# yyb_v2_Leds.net
KiCad netlist of a schematic drawn in Altium Designer
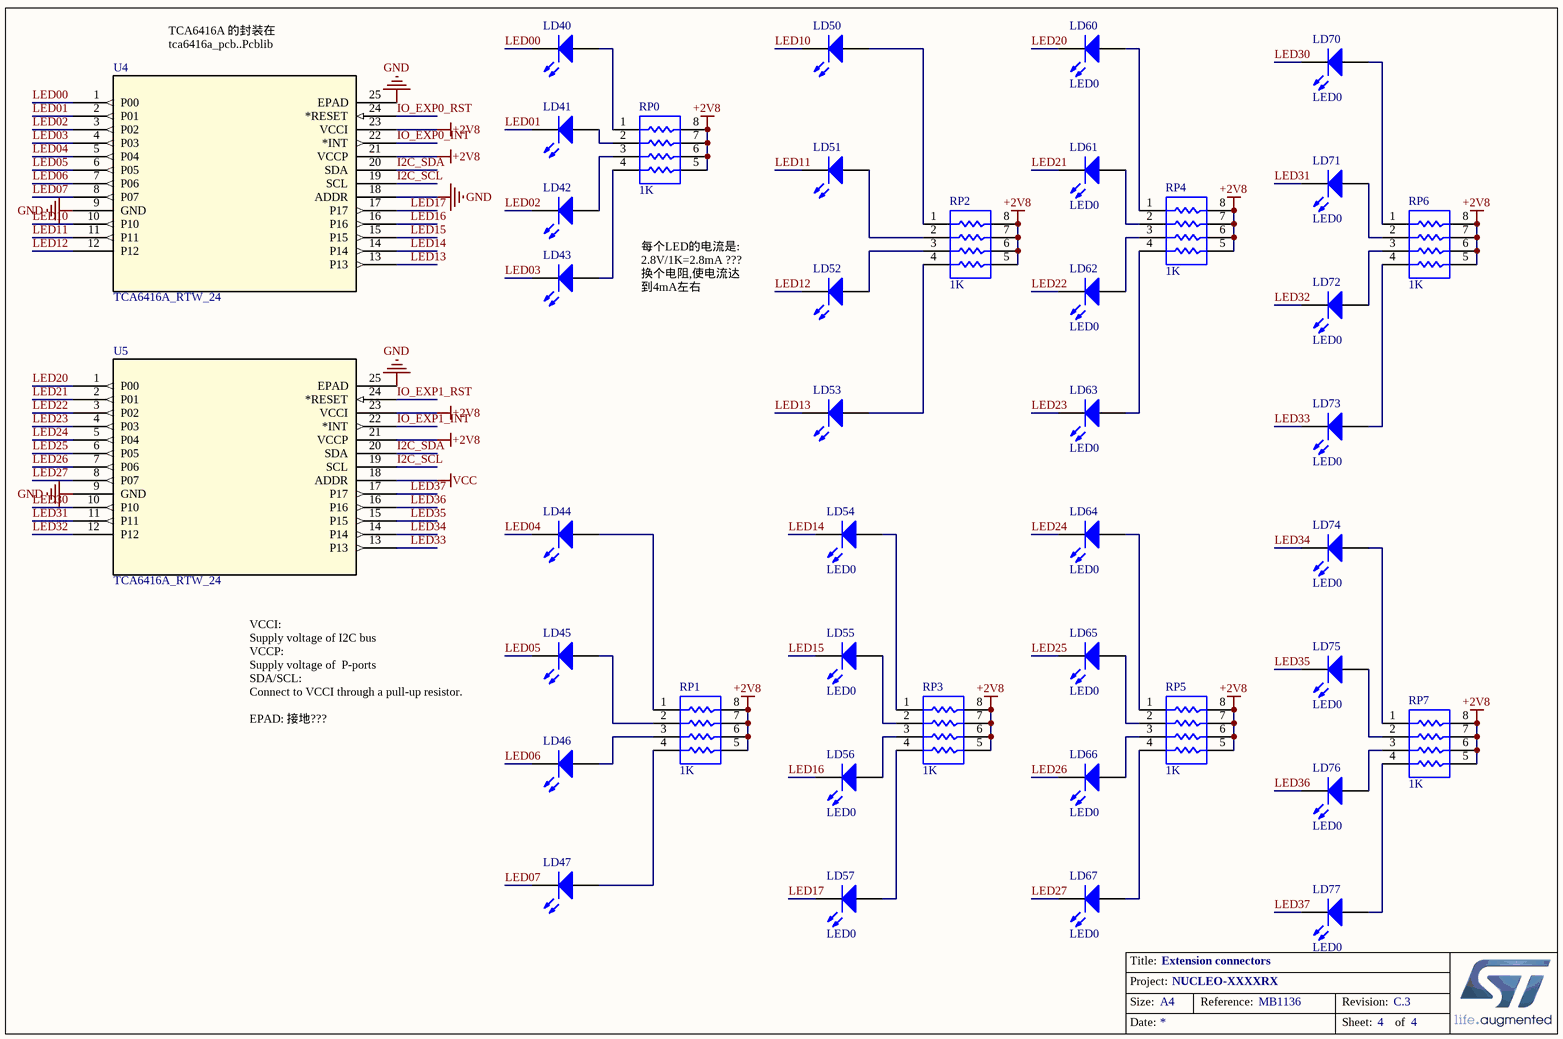
[diagram p0: yyb_v2_Leds.SchDoc]

(export (version "E")
  (design (tool "Eeschema 10.0.6"))
  (components
    (comp (ref "LD40")
      (value "LED0")
      (footprint "LED5")
      (description "Typical INFRARED GaAs LED")
      (fields (field (name "PUBLISHER") "Altium Limited"))
      (libsource (lib "Miscellaneous Devices") (part "LED0"))
    )
    (comp (ref "LD41")
      (value "LED0")
      (footprint "LED5")
      (description "Typical INFRARED GaAs LED")
      (fields (field (name "PUBLISHER") "Altium Limited"))
      (libsource (lib "Miscellaneous Devices") (part "LED0"))
    )
    (comp (ref "LD42")
      (value "LED0")
      (footprint "LED5")
      (description "Typical INFRARED GaAs LED")
      (fields (field (name "PUBLISHER") "Altium Limited"))
      (libsource (lib "Miscellaneous Devices") (part "LED0"))
    )
    (comp (ref "LD43")
      (value "LED0")
      (footprint "LED5")
      (description "Typical INFRARED GaAs LED")
      (fields (field (name "PUBLISHER") "Altium Limited"))
      (libsource (lib "Miscellaneous Devices") (part "LED0"))
    )
    (comp (ref "LD44")
      (value "LED0")
      (footprint "LED-0")
      (description "Typical INFRARED GaAs LED")
      (fields (field (name "PUBLISHER") "Altium Limited"))
      (libsource (lib "Miscellaneous Devices") (part "LED0"))
    )
    (comp (ref "LD45")
      (value "LED0")
      (footprint "LED-0")
      (description "Typical INFRARED GaAs LED")
      (fields (field (name "PUBLISHER") "Altium Limited"))
      (libsource (lib "Miscellaneous Devices") (part "LED0"))
    )
    (comp (ref "LD46")
      (value "LED0")
      (footprint "LED-0")
      (description "Typical INFRARED GaAs LED")
      (fields (field (name "PUBLISHER") "Altium Limited"))
      (libsource (lib "Miscellaneous Devices") (part "LED0"))
    )
    (comp (ref "LD47")
      (value "LED0")
      (footprint "LED-0")
      (description "Typical INFRARED GaAs LED")
      (fields (field (name "PUBLISHER") "Altium Limited"))
      (libsource (lib "Miscellaneous Devices") (part "LED0"))
    )
    (comp (ref "LD50")
      (value "LED0")
      (footprint "LED-0")
      (description "Typical INFRARED GaAs LED")
      (fields (field (name "PUBLISHER") "Altium Limited"))
      (libsource (lib "Miscellaneous Devices") (part "LED0"))
    )
    (comp (ref "LD51")
      (value "LED0")
      (footprint "LED-0")
      (description "Typical INFRARED GaAs LED")
      (fields (field (name "PUBLISHER") "Altium Limited"))
      (libsource (lib "Miscellaneous Devices") (part "LED0"))
    )
    (comp (ref "LD52")
      (value "LED0")
      (footprint "LED-0")
      (description "Typical INFRARED GaAs LED")
      (fields (field (name "PUBLISHER") "Altium Limited"))
      (libsource (lib "Miscellaneous Devices") (part "LED0"))
    )
    (comp (ref "LD53")
      (value "LED0")
      (footprint "LED-0")
      (description "Typical INFRARED GaAs LED")
      (fields (field (name "PUBLISHER") "Altium Limited"))
      (libsource (lib "Miscellaneous Devices") (part "LED0"))
    )
    (comp (ref "LD54")
      (value "LED0")
      (footprint "LED5")
      (description "Typical INFRARED GaAs LED")
      (fields (field (name "PUBLISHER") "Altium Limited"))
      (libsource (lib "Miscellaneous Devices") (part "LED0"))
    )
    (comp (ref "LD55")
      (value "LED0")
      (footprint "LED5")
      (description "Typical INFRARED GaAs LED")
      (fields (field (name "PUBLISHER") "Altium Limited"))
      (libsource (lib "Miscellaneous Devices") (part "LED0"))
    )
    (comp (ref "LD56")
      (value "LED0")
      (footprint "LED5")
      (description "Typical INFRARED GaAs LED")
      (fields (field (name "PUBLISHER") "Altium Limited"))
      (libsource (lib "Miscellaneous Devices") (part "LED0"))
    )
    (comp (ref "LD57")
      (value "LED0")
      (footprint "LED5")
      (description "Typical INFRARED GaAs LED")
      (fields (field (name "PUBLISHER") "Altium Limited"))
      (libsource (lib "Miscellaneous Devices") (part "LED0"))
    )
    (comp (ref "LD60")
      (value "LED0")
      (footprint "LED5")
      (description "Typical INFRARED GaAs LED")
      (fields (field (name "PUBLISHER") "Altium Limited"))
      (libsource (lib "Miscellaneous Devices") (part "LED0"))
    )
    (comp (ref "LD61")
      (value "LED0")
      (footprint "LED5")
      (description "Typical INFRARED GaAs LED")
      (fields (field (name "PUBLISHER") "Altium Limited"))
      (libsource (lib "Miscellaneous Devices") (part "LED0"))
    )
    (comp (ref "LD62")
      (value "LED0")
      (footprint "LED5")
      (description "Typical INFRARED GaAs LED")
      (fields (field (name "PUBLISHER") "Altium Limited"))
      (libsource (lib "Miscellaneous Devices") (part "LED0"))
    )
    (comp (ref "LD63")
      (value "LED0")
      (footprint "LED5")
      (description "Typical INFRARED GaAs LED")
      (fields (field (name "PUBLISHER") "Altium Limited"))
      (libsource (lib "Miscellaneous Devices") (part "LED0"))
    )
    (comp (ref "LD64")
      (value "LED0")
      (footprint "LED5")
      (description "Typical INFRARED GaAs LED")
      (fields (field (name "PUBLISHER") "Altium Limited"))
      (libsource (lib "Miscellaneous Devices") (part "LED0"))
    )
    (comp (ref "LD65")
      (value "LED0")
      (footprint "LED5")
      (description "Typical INFRARED GaAs LED")
      (fields (field (name "PUBLISHER") "Altium Limited"))
      (libsource (lib "Miscellaneous Devices") (part "LED0"))
    )
    (comp (ref "LD66")
      (value "LED0")
      (footprint "LED5")
      (description "Typical INFRARED GaAs LED")
      (fields (field (name "PUBLISHER") "Altium Limited"))
      (libsource (lib "Miscellaneous Devices") (part "LED0"))
    )
    (comp (ref "LD67")
      (value "LED0")
      (footprint "LED5")
      (description "Typical INFRARED GaAs LED")
      (fields (field (name "PUBLISHER") "Altium Limited"))
      (libsource (lib "Miscellaneous Devices") (part "LED0"))
    )
    (comp (ref "LD70")
      (value "LED0")
      (footprint "LED5")
      (description "Typical INFRARED GaAs LED")
      (fields (field (name "PUBLISHER") "Altium Limited"))
      (libsource (lib "Miscellaneous Devices") (part "LED0"))
    )
    (comp (ref "LD71")
      (value "LED0")
      (footprint "LED5")
      (description "Typical INFRARED GaAs LED")
      (fields (field (name "PUBLISHER") "Altium Limited"))
      (libsource (lib "Miscellaneous Devices") (part "LED0"))
    )
    (comp (ref "LD72")
      (value "LED0")
      (footprint "LED5")
      (description "Typical INFRARED GaAs LED")
      (fields (field (name "PUBLISHER") "Altium Limited"))
      (libsource (lib "Miscellaneous Devices") (part "LED0"))
    )
    (comp (ref "LD73")
      (value "LED0")
      (footprint "LED5")
      (description "Typical INFRARED GaAs LED")
      (fields (field (name "PUBLISHER") "Altium Limited"))
      (libsource (lib "Miscellaneous Devices") (part "LED0"))
    )
    (comp (ref "LD74")
      (value "LED0")
      (footprint "LED5")
      (description "Typical INFRARED GaAs LED")
      (fields (field (name "PUBLISHER") "Altium Limited"))
      (libsource (lib "Miscellaneous Devices") (part "LED0"))
    )
    (comp (ref "LD75")
      (value "LED0")
      (footprint "LED5")
      (description "Typical INFRARED GaAs LED")
      (fields (field (name "PUBLISHER") "Altium Limited"))
      (libsource (lib "Miscellaneous Devices") (part "LED0"))
    )
    (comp (ref "LD76")
      (value "LED0")
      (footprint "LED5")
      (description "Typical INFRARED GaAs LED")
      (fields (field (name "PUBLISHER") "Altium Limited"))
      (libsource (lib "Miscellaneous Devices") (part "LED0"))
    )
    (comp (ref "LD77")
      (value "LED0")
      (footprint "LED5")
      (description "Typical INFRARED GaAs LED")
      (fields (field (name "PUBLISHER") "Altium Limited"))
      (libsource (lib "Miscellaneous Devices") (part "LED0"))
    )
    (comp (ref "RP0") (value "1K") (footprint "4P8") (libsource (lib "*") (part "RESPACK3_1")))
    (comp (ref "RP1") (value "1K") (footprint "4P8") (libsource (lib "*") (part "RESPACK3_1")))
    (comp (ref "RP2") (value "1K") (footprint "4P8") (libsource (lib "*") (part "RESPACK3_1")))
    (comp (ref "RP3") (value "1K") (footprint "4P8") (libsource (lib "*") (part "RESPACK3_1")))
    (comp (ref "RP4") (value "1K") (footprint "4P8") (libsource (lib "*") (part "RESPACK3_1")))
    (comp (ref "RP5") (value "1K") (footprint "4P8") (libsource (lib "*") (part "RESPACK3_1")))
    (comp (ref "RP6") (value "1K") (footprint "4P8") (libsource (lib "*") (part "RESPACK3_1")))
    (comp (ref "RP7") (value "1K") (footprint "4P8") (libsource (lib "*") (part "RESPACK3_1")))
    (comp (ref "U4")
      (value "TCA6416A_RTW_24")
      (footprint "RTW24_2P45X2P45")
      (description "Imported")
      (fields
        (field (name "MANUFACTURER") "Texas Instruments")
        (field (name "GENERIC_PART_NUMBER") "TCA6416A")
      )
      (libsource (lib "yyb_sch_layout_v2") (part "TCA6416A_RTW_24"))
    )
    (comp (ref "U5")
      (value "TCA6416A_RTW_24")
      (footprint "RTW24_2P45X2P45")
      (description "Imported")
      (fields
        (field (name "MANUFACTURER") "Texas Instruments")
        (field (name "GENERIC_PART_NUMBER") "TCA6416A")
      )
      (libsource (lib "yyb_sch_layout_v2") (part "TCA6416A_RTW_24"))
    )
  )
  (nets
    (net (code "1") (name "+2V8") (class "Default")
      (node (ref "RP0") (pin "5") (pinfunction "5_5") (pintype "passive"))
      (node (ref "RP0") (pin "6") (pinfunction "6_6") (pintype "passive"))
      (node (ref "RP0") (pin "7") (pinfunction "7_7") (pintype "passive"))
      (node (ref "RP0") (pin "8") (pinfunction "8_8") (pintype "passive"))
      (node (ref "RP1") (pin "5") (pinfunction "5_5") (pintype "passive"))
      (node (ref "RP1") (pin "6") (pinfunction "6_6") (pintype "passive"))
      (node (ref "RP1") (pin "7") (pinfunction "7_7") (pintype "passive"))
      (node (ref "RP1") (pin "8") (pinfunction "8_8") (pintype "passive"))
      (node (ref "RP2") (pin "5") (pinfunction "5_5") (pintype "passive"))
      (node (ref "RP2") (pin "6") (pinfunction "6_6") (pintype "passive"))
      (node (ref "RP2") (pin "7") (pinfunction "7_7") (pintype "passive"))
      (node (ref "RP2") (pin "8") (pinfunction "8_8") (pintype "passive"))
      (node (ref "RP3") (pin "5") (pinfunction "5_5") (pintype "passive"))
      (node (ref "RP3") (pin "6") (pinfunction "6_6") (pintype "passive"))
      (node (ref "RP3") (pin "7") (pinfunction "7_7") (pintype "passive"))
      (node (ref "RP3") (pin "8") (pinfunction "8_8") (pintype "passive"))
      (node (ref "RP4") (pin "5") (pinfunction "5_5") (pintype "passive"))
      (node (ref "RP4") (pin "6") (pinfunction "6_6") (pintype "passive"))
      (node (ref "RP4") (pin "7") (pinfunction "7_7") (pintype "passive"))
      (node (ref "RP4") (pin "8") (pinfunction "8_8") (pintype "passive"))
      (node (ref "RP5") (pin "5") (pinfunction "5_5") (pintype "passive"))
      (node (ref "RP5") (pin "6") (pinfunction "6_6") (pintype "passive"))
      (node (ref "RP5") (pin "7") (pinfunction "7_7") (pintype "passive"))
      (node (ref "RP5") (pin "8") (pinfunction "8_8") (pintype "passive"))
      (node (ref "RP6") (pin "5") (pinfunction "5_5") (pintype "passive"))
      (node (ref "RP6") (pin "6") (pinfunction "6_6") (pintype "passive"))
      (node (ref "RP6") (pin "7") (pinfunction "7_7") (pintype "passive"))
      (node (ref "RP6") (pin "8") (pinfunction "8_8") (pintype "passive"))
      (node (ref "RP7") (pin "5") (pinfunction "5_5") (pintype "passive"))
      (node (ref "RP7") (pin "6") (pinfunction "6_6") (pintype "passive"))
      (node (ref "RP7") (pin "7") (pinfunction "7_7") (pintype "passive"))
      (node (ref "RP7") (pin "8") (pinfunction "8_8") (pintype "passive"))
      (node (ref "U4") (pin "21") (pinfunction "VCCP_21") (pintype "power_in"))
      (node (ref "U4") (pin "23") (pinfunction "VCCI_23") (pintype "power_in"))
      (node (ref "U5") (pin "21") (pinfunction "VCCP_21") (pintype "power_in"))
      (node (ref "U5") (pin "23") (pinfunction "VCCI_23") (pintype "power_in"))
    )
    (net (code "2") (name "/I2C_SCL") (class "Default")
      (node (ref "U4") (pin "19") (pinfunction "SCL_19") (pintype "passive"))
      (node (ref "U5") (pin "19") (pinfunction "SCL_19") (pintype "passive"))
    )
    (net (code "3") (name "/I2C_SDA") (class "Default")
      (node (ref "U4") (pin "20") (pinfunction "SDA_20") (pintype "passive"))
      (node (ref "U5") (pin "20") (pinfunction "SDA_20") (pintype "passive"))
    )
    (net (code "4") (name "/IO_EXP0_INT") (class "Default")
      (node (ref "U4") (pin "22") (pinfunction "*INT_22") (pintype "output"))
    )
    (net (code "5") (name "/IO_EXP0_RST") (class "Default")
      (node (ref "U4") (pin "24") (pinfunction "*RESET_24") (pintype "input"))
    )
    (net (code "6") (name "/IO_EXP1_INT") (class "Default")
      (node (ref "U5") (pin "22") (pinfunction "*INT_22") (pintype "output"))
    )
    (net (code "7") (name "/IO_EXP1_RST") (class "Default")
      (node (ref "U5") (pin "24") (pinfunction "*RESET_24") (pintype "input"))
    )
    (net (code "8") (name "/LED00") (class "Default")
      (node (ref "LD40") (pin "2") (pinfunction "K_2") (pintype "passive"))
      (node (ref "U4") (pin "1") (pinfunction "P00_1") (pintype "output"))
    )
    (net (code "9") (name "/LED01") (class "Default")
      (node (ref "LD41") (pin "2") (pinfunction "K_2") (pintype "passive"))
      (node (ref "U4") (pin "2") (pinfunction "P01_2") (pintype "output"))
    )
    (net (code "10") (name "/LED02") (class "Default")
      (node (ref "LD42") (pin "2") (pinfunction "K_2") (pintype "passive"))
      (node (ref "U4") (pin "3") (pinfunction "P02_3") (pintype "output"))
    )
    (net (code "11") (name "/LED03") (class "Default")
      (node (ref "LD43") (pin "2") (pinfunction "K_2") (pintype "passive"))
      (node (ref "U4") (pin "4") (pinfunction "P03_4") (pintype "output"))
    )
    (net (code "12") (name "/LED04") (class "Default")
      (node (ref "LD44") (pin "2") (pinfunction "K_2") (pintype "passive"))
      (node (ref "U4") (pin "5") (pinfunction "P04_5") (pintype "output"))
    )
    (net (code "13") (name "/LED05") (class "Default")
      (node (ref "LD45") (pin "2") (pinfunction "K_2") (pintype "passive"))
      (node (ref "U4") (pin "6") (pinfunction "P05_6") (pintype "output"))
    )
    (net (code "14") (name "/LED06") (class "Default")
      (node (ref "LD46") (pin "2") (pinfunction "K_2") (pintype "passive"))
      (node (ref "U4") (pin "7") (pinfunction "P06_7") (pintype "output"))
    )
    (net (code "15") (name "/LED07") (class "Default")
      (node (ref "LD47") (pin "2") (pinfunction "K_2") (pintype "passive"))
      (node (ref "U4") (pin "8") (pinfunction "P07_8") (pintype "output"))
    )
    (net (code "16") (name "/LED10") (class "Default")
      (node (ref "LD50") (pin "2") (pinfunction "K_2") (pintype "passive"))
      (node (ref "U4") (pin "10") (pinfunction "P10_10") (pintype "output"))
    )
    (net (code "17") (name "/LED11") (class "Default")
      (node (ref "LD51") (pin "2") (pinfunction "K_2") (pintype "passive"))
      (node (ref "U4") (pin "11") (pinfunction "P11_11") (pintype "output"))
    )
    (net (code "18") (name "/LED12") (class "Default")
      (node (ref "LD52") (pin "2") (pinfunction "K_2") (pintype "passive"))
      (node (ref "U4") (pin "12") (pinfunction "P12_12") (pintype "power_in"))
    )
    (net (code "19") (name "/LED13") (class "Default")
      (node (ref "LD53") (pin "2") (pinfunction "K_2") (pintype "passive"))
      (node (ref "U4") (pin "13") (pinfunction "P13_13") (pintype "output"))
    )
    (net (code "20") (name "/LED14") (class "Default")
      (node (ref "LD54") (pin "2") (pinfunction "K_2") (pintype "passive"))
      (node (ref "U4") (pin "14") (pinfunction "P14_14") (pintype "output"))
    )
    (net (code "21") (name "/LED15") (class "Default")
      (node (ref "LD55") (pin "2") (pinfunction "K_2") (pintype "passive"))
      (node (ref "U4") (pin "15") (pinfunction "P15_15") (pintype "output"))
    )
    (net (code "22") (name "/LED16") (class "Default")
      (node (ref "LD56") (pin "2") (pinfunction "K_2") (pintype "passive"))
      (node (ref "U4") (pin "16") (pinfunction "P16_16") (pintype "output"))
    )
    (net (code "23") (name "/LED17") (class "Default")
      (node (ref "LD57") (pin "2") (pinfunction "K_2") (pintype "passive"))
      (node (ref "U4") (pin "17") (pinfunction "P17_17") (pintype "output"))
    )
    (net (code "24") (name "/LED20") (class "Default")
      (node (ref "LD60") (pin "2") (pinfunction "K_2") (pintype "passive"))
      (node (ref "U5") (pin "1") (pinfunction "P00_1") (pintype "output"))
    )
    (net (code "25") (name "/LED21") (class "Default")
      (node (ref "LD61") (pin "2") (pinfunction "K_2") (pintype "passive"))
      (node (ref "U5") (pin "2") (pinfunction "P01_2") (pintype "output"))
    )
    (net (code "26") (name "/LED22") (class "Default")
      (node (ref "LD62") (pin "2") (pinfunction "K_2") (pintype "passive"))
      (node (ref "U5") (pin "3") (pinfunction "P02_3") (pintype "output"))
    )
    (net (code "27") (name "/LED23") (class "Default")
      (node (ref "LD63") (pin "2") (pinfunction "K_2") (pintype "passive"))
      (node (ref "U5") (pin "4") (pinfunction "P03_4") (pintype "output"))
    )
    (net (code "28") (name "/LED24") (class "Default")
      (node (ref "LD64") (pin "2") (pinfunction "K_2") (pintype "passive"))
      (node (ref "U5") (pin "5") (pinfunction "P04_5") (pintype "output"))
    )
    (net (code "29") (name "/LED25") (class "Default")
      (node (ref "LD65") (pin "2") (pinfunction "K_2") (pintype "passive"))
      (node (ref "U5") (pin "6") (pinfunction "P05_6") (pintype "output"))
    )
    (net (code "30") (name "/LED26") (class "Default")
      (node (ref "LD66") (pin "2") (pinfunction "K_2") (pintype "passive"))
      (node (ref "U5") (pin "7") (pinfunction "P06_7") (pintype "output"))
    )
    (net (code "31") (name "/LED27") (class "Default")
      (node (ref "LD67") (pin "2") (pinfunction "K_2") (pintype "passive"))
      (node (ref "U5") (pin "8") (pinfunction "P07_8") (pintype "output"))
    )
    (net (code "32") (name "/LED30") (class "Default")
      (node (ref "LD70") (pin "2") (pinfunction "K_2") (pintype "passive"))
      (node (ref "U5") (pin "10") (pinfunction "P10_10") (pintype "output"))
    )
    (net (code "33") (name "/LED31") (class "Default")
      (node (ref "LD71") (pin "2") (pinfunction "K_2") (pintype "passive"))
      (node (ref "U5") (pin "11") (pinfunction "P11_11") (pintype "output"))
    )
    (net (code "34") (name "/LED32") (class "Default")
      (node (ref "LD72") (pin "2") (pinfunction "K_2") (pintype "passive"))
      (node (ref "U5") (pin "12") (pinfunction "P12_12") (pintype "power_in"))
    )
    (net (code "35") (name "/LED33") (class "Default")
      (node (ref "LD73") (pin "2") (pinfunction "K_2") (pintype "passive"))
      (node (ref "U5") (pin "13") (pinfunction "P13_13") (pintype "output"))
    )
    (net (code "36") (name "/LED34") (class "Default")
      (node (ref "LD74") (pin "2") (pinfunction "K_2") (pintype "passive"))
      (node (ref "U5") (pin "14") (pinfunction "P14_14") (pintype "output"))
    )
    (net (code "37") (name "/LED35") (class "Default")
      (node (ref "LD75") (pin "2") (pinfunction "K_2") (pintype "passive"))
      (node (ref "U5") (pin "15") (pinfunction "P15_15") (pintype "output"))
    )
    (net (code "38") (name "/LED36") (class "Default")
      (node (ref "LD76") (pin "2") (pinfunction "K_2") (pintype "passive"))
      (node (ref "U5") (pin "16") (pinfunction "P16_16") (pintype "output"))
    )
    (net (code "39") (name "/LED37") (class "Default")
      (node (ref "LD77") (pin "2") (pinfunction "K_2") (pintype "passive"))
      (node (ref "U5") (pin "17") (pinfunction "P17_17") (pintype "output"))
    )
    (net (code "40") (name "GND") (class "Default")
      (node (ref "U4") (pin "18") (pinfunction "ADDR_18") (pintype "passive"))
      (node (ref "U4") (pin "25") (pinfunction "EPAD_25") (pintype "passive"))
      (node (ref "U4") (pin "9") (pinfunction "GND_9") (pintype "power_in"))
      (node (ref "U5") (pin "25") (pinfunction "EPAD_25") (pintype "passive"))
      (node (ref "U5") (pin "9") (pinfunction "GND_9") (pintype "power_in"))
    )
    (net (code "41") (name "Net-(LD40-A)") (class "Default")
      (node (ref "LD40") (pin "1") (pinfunction "A_1") (pintype "passive"))
      (node (ref "RP0") (pin "1") (pinfunction "1_1") (pintype "passive"))
    )
    (net (code "42") (name "Net-(LD41-A)") (class "Default")
      (node (ref "LD41") (pin "1") (pinfunction "A_1") (pintype "passive"))
      (node (ref "RP0") (pin "2") (pinfunction "2_2") (pintype "passive"))
    )
    (net (code "43") (name "Net-(LD42-A)") (class "Default")
      (node (ref "LD42") (pin "1") (pinfunction "A_1") (pintype "passive"))
      (node (ref "RP0") (pin "3") (pinfunction "3_3") (pintype "passive"))
    )
    (net (code "44") (name "Net-(LD43-A)") (class "Default")
      (node (ref "LD43") (pin "1") (pinfunction "A_1") (pintype "passive"))
      (node (ref "RP0") (pin "4") (pinfunction "4_4") (pintype "passive"))
    )
    (net (code "45") (name "Net-(LD44-A)") (class "Default")
      (node (ref "LD44") (pin "1") (pinfunction "A_1") (pintype "passive"))
      (node (ref "RP1") (pin "1") (pinfunction "1_1") (pintype "passive"))
    )
    (net (code "46") (name "Net-(LD45-A)") (class "Default")
      (node (ref "LD45") (pin "1") (pinfunction "A_1") (pintype "passive"))
      (node (ref "RP1") (pin "2") (pinfunction "2_2") (pintype "passive"))
    )
    (net (code "47") (name "Net-(LD46-A)") (class "Default")
      (node (ref "LD46") (pin "1") (pinfunction "A_1") (pintype "passive"))
      (node (ref "RP1") (pin "3") (pinfunction "3_3") (pintype "passive"))
    )
    (net (code "48") (name "Net-(LD47-A)") (class "Default")
      (node (ref "LD47") (pin "1") (pinfunction "A_1") (pintype "passive"))
      (node (ref "RP1") (pin "4") (pinfunction "4_4") (pintype "passive"))
    )
    (net (code "49") (name "Net-(LD50-A)") (class "Default")
      (node (ref "LD50") (pin "1") (pinfunction "A_1") (pintype "passive"))
      (node (ref "RP2") (pin "1") (pinfunction "1_1") (pintype "passive"))
    )
    (net (code "50") (name "Net-(LD51-A)") (class "Default")
      (node (ref "LD51") (pin "1") (pinfunction "A_1") (pintype "passive"))
      (node (ref "RP2") (pin "2") (pinfunction "2_2") (pintype "passive"))
    )
    (net (code "51") (name "Net-(LD52-A)") (class "Default")
      (node (ref "LD52") (pin "1") (pinfunction "A_1") (pintype "passive"))
      (node (ref "RP2") (pin "3") (pinfunction "3_3") (pintype "passive"))
    )
    (net (code "52") (name "Net-(LD53-A)") (class "Default")
      (node (ref "LD53") (pin "1") (pinfunction "A_1") (pintype "passive"))
      (node (ref "RP2") (pin "4") (pinfunction "4_4") (pintype "passive"))
    )
    (net (code "53") (name "Net-(LD54-A)") (class "Default")
      (node (ref "LD54") (pin "1") (pinfunction "A_1") (pintype "passive"))
      (node (ref "RP3") (pin "1") (pinfunction "1_1") (pintype "passive"))
    )
    (net (code "54") (name "Net-(LD55-A)") (class "Default")
      (node (ref "LD55") (pin "1") (pinfunction "A_1") (pintype "passive"))
      (node (ref "RP3") (pin "2") (pinfunction "2_2") (pintype "passive"))
    )
    (net (code "55") (name "Net-(LD56-A)") (class "Default")
      (node (ref "LD56") (pin "1") (pinfunction "A_1") (pintype "passive"))
      (node (ref "RP3") (pin "3") (pinfunction "3_3") (pintype "passive"))
    )
    (net (code "56") (name "Net-(LD57-A)") (class "Default")
      (node (ref "LD57") (pin "1") (pinfunction "A_1") (pintype "passive"))
      (node (ref "RP3") (pin "4") (pinfunction "4_4") (pintype "passive"))
    )
    (net (code "57") (name "Net-(LD60-A)") (class "Default")
      (node (ref "LD60") (pin "1") (pinfunction "A_1") (pintype "passive"))
      (node (ref "RP4") (pin "1") (pinfunction "1_1") (pintype "passive"))
    )
    (net (code "58") (name "Net-(LD61-A)") (class "Default")
      (node (ref "LD61") (pin "1") (pinfunction "A_1") (pintype "passive"))
      (node (ref "RP4") (pin "2") (pinfunction "2_2") (pintype "passive"))
    )
    (net (code "59") (name "Net-(LD62-A)") (class "Default")
      (node (ref "LD62") (pin "1") (pinfunction "A_1") (pintype "passive"))
      (node (ref "RP4") (pin "3") (pinfunction "3_3") (pintype "passive"))
    )
    (net (code "60") (name "Net-(LD63-A)") (class "Default")
      (node (ref "LD63") (pin "1") (pinfunction "A_1") (pintype "passive"))
      (node (ref "RP4") (pin "4") (pinfunction "4_4") (pintype "passive"))
    )
    (net (code "61") (name "Net-(LD64-A)") (class "Default")
      (node (ref "LD64") (pin "1") (pinfunction "A_1") (pintype "passive"))
      (node (ref "RP5") (pin "1") (pinfunction "1_1") (pintype "passive"))
    )
    (net (code "62") (name "Net-(LD65-A)") (class "Default")
      (node (ref "LD65") (pin "1") (pinfunction "A_1") (pintype "passive"))
      (node (ref "RP5") (pin "2") (pinfunction "2_2") (pintype "passive"))
    )
    (net (code "63") (name "Net-(LD66-A)") (class "Default")
      (node (ref "LD66") (pin "1") (pinfunction "A_1") (pintype "passive"))
      (node (ref "RP5") (pin "3") (pinfunction "3_3") (pintype "passive"))
    )
    (net (code "64") (name "Net-(LD67-A)") (class "Default")
      (node (ref "LD67") (pin "1") (pinfunction "A_1") (pintype "passive"))
      (node (ref "RP5") (pin "4") (pinfunction "4_4") (pintype "passive"))
    )
    (net (code "65") (name "Net-(LD70-A)") (class "Default")
      (node (ref "LD70") (pin "1") (pinfunction "A_1") (pintype "passive"))
      (node (ref "RP6") (pin "1") (pinfunction "1_1") (pintype "passive"))
    )
    (net (code "66") (name "Net-(LD71-A)") (class "Default")
      (node (ref "LD71") (pin "1") (pinfunction "A_1") (pintype "passive"))
      (node (ref "RP6") (pin "2") (pinfunction "2_2") (pintype "passive"))
    )
    (net (code "67") (name "Net-(LD72-A)") (class "Default")
      (node (ref "LD72") (pin "1") (pinfunction "A_1") (pintype "passive"))
      (node (ref "RP6") (pin "3") (pinfunction "3_3") (pintype "passive"))
    )
    (net (code "68") (name "Net-(LD73-A)") (class "Default")
      (node (ref "LD73") (pin "1") (pinfunction "A_1") (pintype "passive"))
      (node (ref "RP6") (pin "4") (pinfunction "4_4") (pintype "passive"))
    )
    (net (code "69") (name "Net-(LD74-A)") (class "Default")
      (node (ref "LD74") (pin "1") (pinfunction "A_1") (pintype "passive"))
      (node (ref "RP7") (pin "1") (pinfunction "1_1") (pintype "passive"))
    )
    (net (code "70") (name "Net-(LD75-A)") (class "Default")
      (node (ref "LD75") (pin "1") (pinfunction "A_1") (pintype "passive"))
      (node (ref "RP7") (pin "2") (pinfunction "2_2") (pintype "passive"))
    )
    (net (code "71") (name "Net-(LD76-A)") (class "Default")
      (node (ref "LD76") (pin "1") (pinfunction "A_1") (pintype "passive"))
      (node (ref "RP7") (pin "3") (pinfunction "3_3") (pintype "passive"))
    )
    (net (code "72") (name "Net-(LD77-A)") (class "Default")
      (node (ref "LD77") (pin "1") (pinfunction "A_1") (pintype "passive"))
      (node (ref "RP7") (pin "4") (pinfunction "4_4") (pintype "passive"))
    )
    (net (code "73") (name "VCC") (class "Default")
      (node (ref "U5") (pin "18") (pinfunction "ADDR_18") (pintype "passive"))
    )
  )
)
